# IF.net
KiCad netlist of a schematic drawn in EAGLE
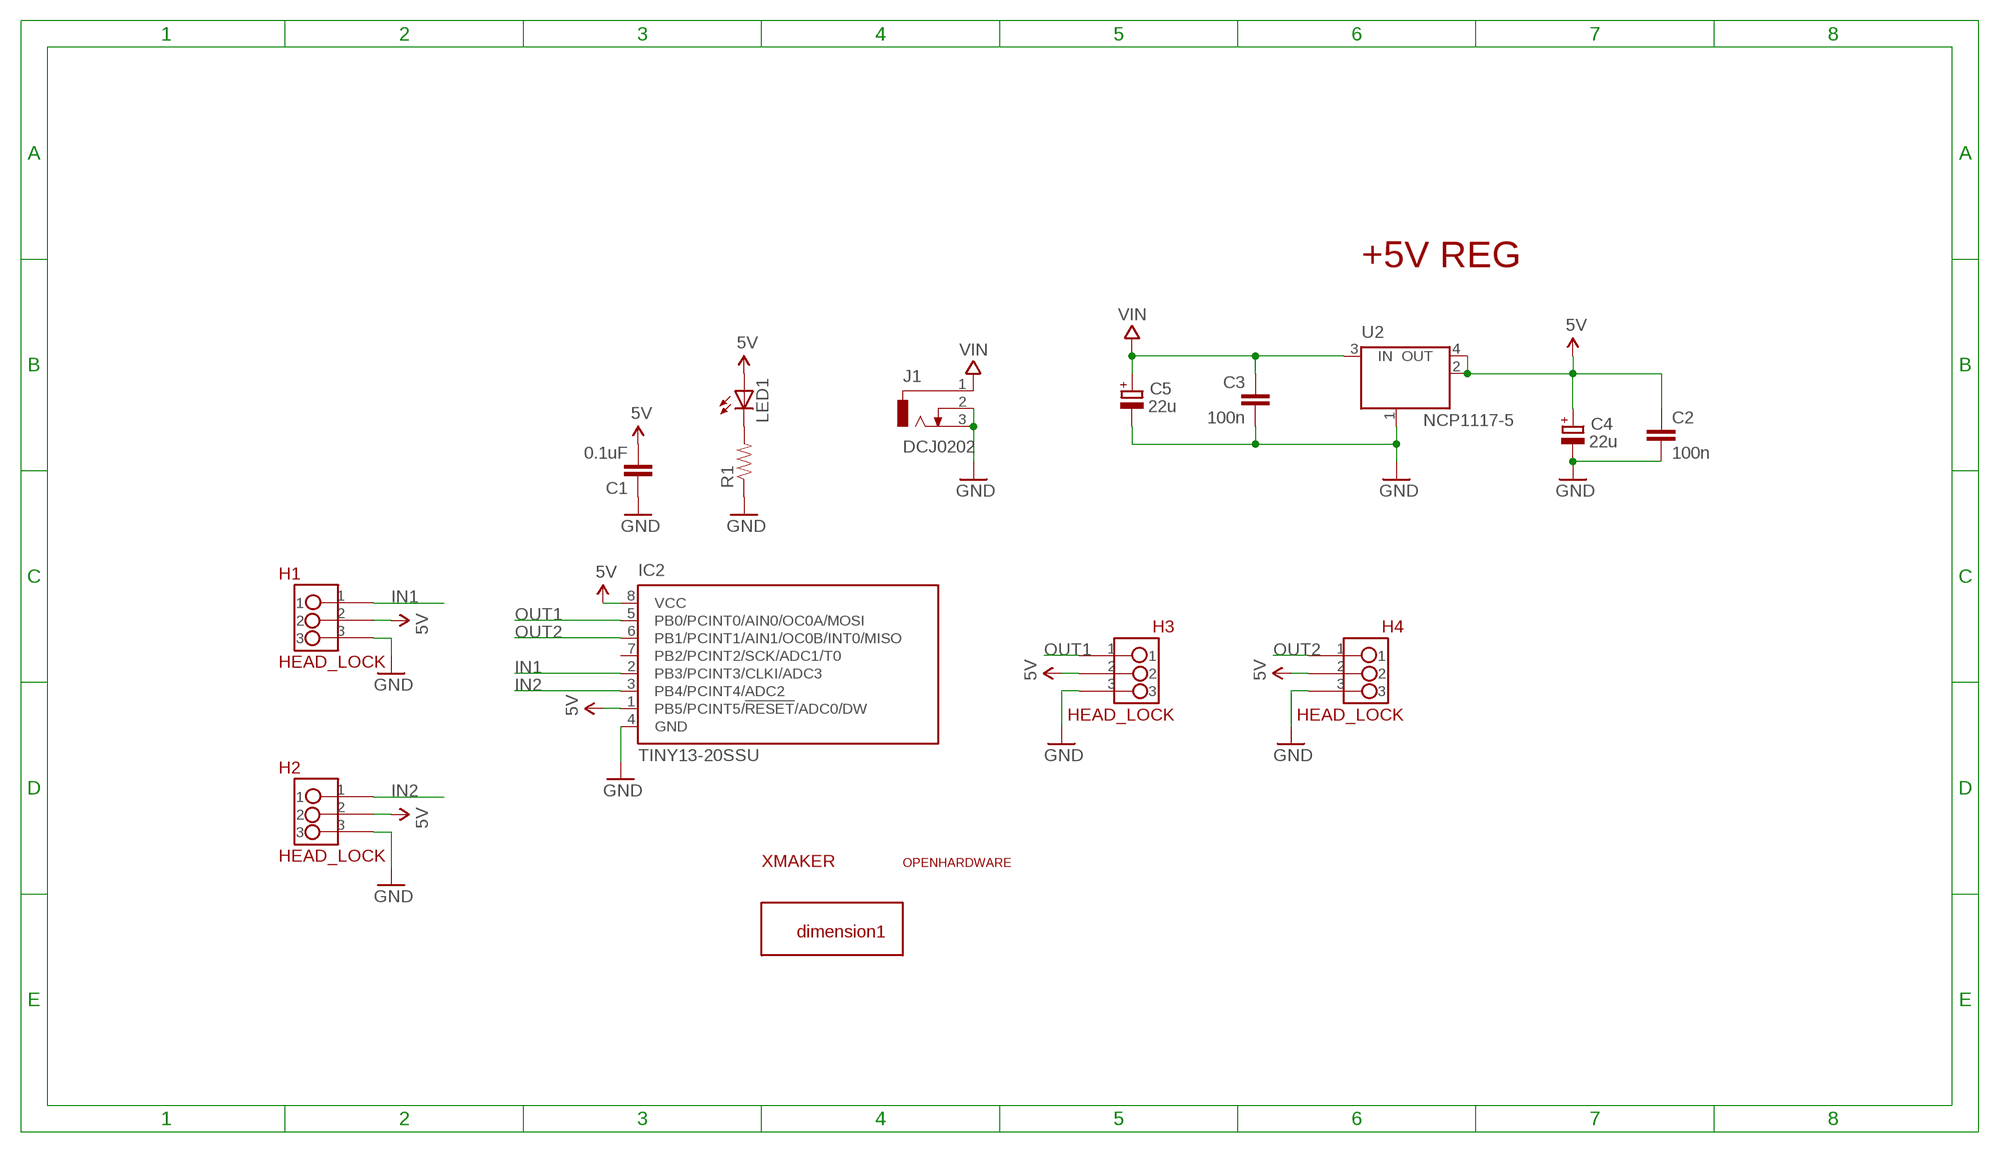
[diagram p0: schematic, sheet 1]

(export (version "E")
  (design (tool "Eeschema 10.0.6"))
  (components
    (comp (ref "C1")
      (value "0.1uF")
      (footprint "eagle-import:0603-CAP")
      (libsource (lib "eagle-import") (part "0.1UF-25V(+80/-20%)(0603)"))
    )
    (comp (ref "C2")
      (value "100n")
      (footprint "eagle-import:C0402")
      (libsource (lib "eagle-import") (part "C-EUC0402"))
    )
    (comp (ref "C3")
      (value "100n")
      (footprint "eagle-import:C0402")
      (libsource (lib "eagle-import") (part "C-EUC0402"))
    )
    (comp (ref "C4")
      (value "22u")
      (footprint "eagle-import:SMC_B")
      (libsource (lib "eagle-import") (part "CPOL-EUSMCB"))
    )
    (comp (ref "C5")
      (value "22u")
      (footprint "eagle-import:SMC_B")
      (libsource (lib "eagle-import") (part "CPOL-EUSMCB"))
    )
    (comp (ref "H1")
      (value "HEAD_LOCK")
      (footprint "eagle-import:HEAD_LOCK")
      (libsource (lib "eagle-import") (part "HEAD_LOCK"))
    )
    (comp (ref "H2")
      (value "HEAD_LOCK")
      (footprint "eagle-import:HEAD_LOCK")
      (libsource (lib "eagle-import") (part "HEAD_LOCK"))
    )
    (comp (ref "H3")
      (value "HEAD_LOCK")
      (footprint "eagle-import:HEAD_LOCK")
      (libsource (lib "eagle-import") (part "HEAD_LOCK"))
    )
    (comp (ref "H4")
      (value "HEAD_LOCK")
      (footprint "eagle-import:HEAD_LOCK")
      (libsource (lib "eagle-import") (part "HEAD_LOCK"))
    )
    (comp (ref "IC2")
      (value "TINY13-20SSU")
      (footprint "eagle-import:8S1")
      (fields (field (name "MPN") "ATTINY13-20SSU"))
      (libsource (lib "eagle-import") (part "TINY13SSU-20"))
    )
    (comp (ref "J1")
      (value "DCJ0202")
      (footprint "eagle-import:DCJ0202")
      (libsource (lib "eagle-import") (part "DCJ0202"))
    )
    (comp (ref "LED1")
      (value "LEDSML0603")
      (footprint "eagle-import:SML0603")
      (libsource (lib "eagle-import") (part "LEDSML0603"))
    )
    (comp (ref "R1")
      (value "RESISTOR0603-RES")
      (footprint "eagle-import:0603-RES")
      (libsource (lib "eagle-import") (part "RESISTOR0603-RES"))
    )
    (comp (ref "U$2")
      (value "XMAKERLOGO2")
      (footprint "eagle-import:XMAKERLOGO2")
      (libsource (lib "eagle-import") (part "XMAKERLOGO2"))
    )
    (comp (ref "U$3")
      (value "OPENHARDWARE")
      (footprint "eagle-import:OPENHARDWARE")
      (libsource (lib "eagle-import") (part "OPENHARDWARE"))
    )
    (comp (ref "U$4")
      (value "DIMENSION1")
      (footprint "eagle-import:DIMENSION1")
      (libsource (lib "eagle-import") (part "DIMENSION1"))
    )
    (comp (ref "U2")
      (value "NCP1117-5")
      (footprint "eagle-import:LINEAR_SOT223")
      (libsource (lib "eagle-import") (part "LINEAR_MC33269ST"))
    )
  )
  (nets
    (net (code "1") (name "/IN1") (class "Default")
      (node (ref "H1") (pin "1") (pinfunction "1_1") (pintype "passive"))
      (node (ref "IC2") (pin "2") (pinfunction "PB3/PCINT3/CLKI/ADC3_2") (pintype "bidirectional"))
    )
    (net (code "2") (name "/IN2") (class "Default")
      (node (ref "H2") (pin "1") (pinfunction "1_1") (pintype "passive"))
      (node (ref "IC2") (pin "3") (pinfunction "PB4/PCINT4/ADC2_3") (pintype "bidirectional"))
    )
    (net (code "3") (name "/OUT1") (class "Default")
      (node (ref "H3") (pin "1") (pinfunction "1_1") (pintype "passive"))
      (node (ref "IC2") (pin "5") (pinfunction "PB0/PCINT0/AIN0/OC0A/MOSI_5") (pintype "bidirectional"))
    )
    (net (code "4") (name "/OUT2") (class "Default")
      (node (ref "H4") (pin "1") (pinfunction "1_1") (pintype "passive"))
      (node (ref "IC2") (pin "6") (pinfunction "PB1/PCINT1/AIN1/OC0B/INT0/MISO_6") (pintype "bidirectional"))
    )
    (net (code "5") (name "5V") (class "Default")
      (node (ref "C1") (pin "2") (pinfunction "2_2") (pintype "passive"))
      (node (ref "C2") (pin "1") (pinfunction "1_1") (pintype "passive"))
      (node (ref "C4") (pin "+") (pinfunction "+_+") (pintype "passive"))
      (node (ref "H1") (pin "2") (pinfunction "2_2") (pintype "passive"))
      (node (ref "H2") (pin "2") (pinfunction "2_2") (pintype "passive"))
      (node (ref "H3") (pin "2") (pinfunction "2_2") (pintype "passive"))
      (node (ref "H4") (pin "2") (pinfunction "2_2") (pintype "passive"))
      (node (ref "IC2") (pin "1") (pinfunction "PB5/PCINT5/~{RESET}/ADC0/DW_1") (pintype "bidirectional"))
      (node (ref "IC2") (pin "8") (pinfunction "VCC_8") (pintype "power_in"))
      (node (ref "LED1") (pin "A") (pinfunction "A_A") (pintype "passive"))
      (node (ref "U2") (pin "2") (pinfunction "OUT_2") (pintype "passive"))
      (node (ref "U2") (pin "4") (pinfunction "OUT_4") (pintype "passive"))
    )
    (net (code "6") (name "GND") (class "Default")
      (node (ref "C1") (pin "1") (pinfunction "1_1") (pintype "passive"))
      (node (ref "C2") (pin "2") (pinfunction "2_2") (pintype "passive"))
      (node (ref "C3") (pin "2") (pinfunction "2_2") (pintype "passive"))
      (node (ref "C4") (pin "-") (pinfunction "-_-") (pintype "passive"))
      (node (ref "C5") (pin "-") (pinfunction "-_-") (pintype "passive"))
      (node (ref "H1") (pin "3") (pinfunction "3_3") (pintype "passive"))
      (node (ref "H2") (pin "3") (pinfunction "3_3") (pintype "passive"))
      (node (ref "H3") (pin "3") (pinfunction "3_3") (pintype "passive"))
      (node (ref "H4") (pin "3") (pinfunction "3_3") (pintype "passive"))
      (node (ref "IC2") (pin "4") (pinfunction "GND_4") (pintype "power_in"))
      (node (ref "J1") (pin "2") (pinfunction "2_2") (pintype "passive"))
      (node (ref "J1") (pin "3") (pinfunction "3_3") (pintype "passive"))
      (node (ref "R1") (pin "1") (pinfunction "1_1") (pintype "passive"))
      (node (ref "U2") (pin "1") (pinfunction "GND/ADJ_1") (pintype "input"))
    )
    (net (code "7") (name "Net-(LED1-PadC)") (class "Default")
      (node (ref "LED1") (pin "C") (pinfunction "C_C") (pintype "passive"))
      (node (ref "R1") (pin "2") (pinfunction "2_2") (pintype "passive"))
    )
    (net (code "8") (name "VIN") (class "Default")
      (node (ref "C3") (pin "1") (pinfunction "1_1") (pintype "passive"))
      (node (ref "C5") (pin "+") (pinfunction "+_+") (pintype "passive"))
      (node (ref "J1") (pin "1") (pinfunction "1_1") (pintype "passive"))
      (node (ref "U2") (pin "3") (pinfunction "IN_3") (pintype "input"))
    )
    (net (code "9") (name "unconnected-(IC2-PB2{slash}PCINT2{slash}SCK{slash}ADC1{slash}T0-Pad7)") (class "Default")
      (node (ref "IC2") (pin "7") (pinfunction "PB2/PCINT2/SCK/ADC1/T0_7") (pintype "bidirectional"))
    )
  )
)
